# 12-Power-P3V3.net
KiCad netlist of a schematic drawn in Altium Designer
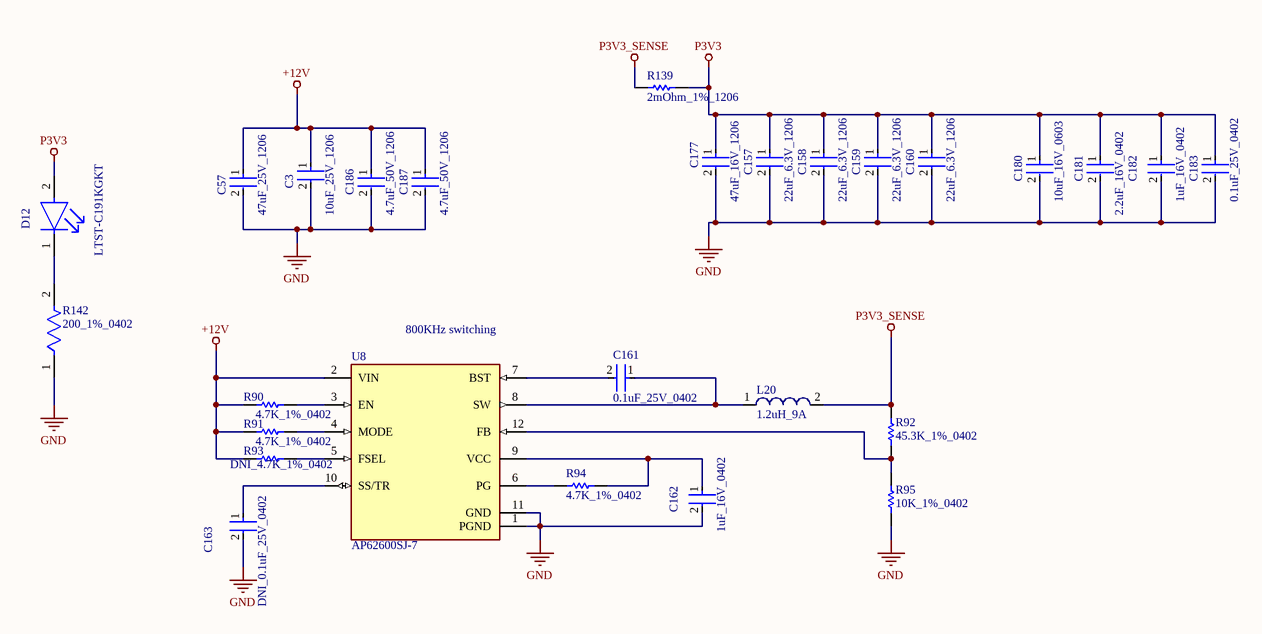
[diagram p0: 12-Power-P3V3.SchDoc]

(export (version "E")
  (design (tool "Eeschema 10.0.6"))
  (components
    (comp (ref "C3")
      (value "10uF_25V_1206")
      (footprint "FP-1206-L_3_2_0_2-W_1_6_0-IPC_A")
      (description "General Purpose Ceramic Capacitor, 1206, 10uF, 20%, X5R, 15%, 25V")
      (fields (field (name "TOLERANCE") "20%"))
      (libsource (lib "Altium Content Vault") (part "02cd4be3c70576c341d710602a673aa"))
    )
    (comp (ref "C57")
      (value "47uF_25V_1206")
      (footprint "FP-C3216-160-0_2-MFG")
      (description "Multilayer Ceramic Capacitors 47uF ±20% 25V X5R SMD 1206")
      (fields (field (name "VOLTAGE") "25V") (field (name "TOLERANCE") "20%"))
      (libsource (lib "Altium Content Vault") (part "11868f565c42a9108669ba33697ecf6"))
    )
    (comp (ref "C157")
      (value "22uF_6.3V_1206")
      (footprint "FP-1206-L_3_2_0_2-W_1_6_0-IPC_C")
      (description "General Purpose Ceramic Capacitor, 1206, 22uF, 20%, X5R, 15%, 6.3V")
      (fields (field (name "TOLERANCE") "20%") (field (name "VOLTAGE") "6.3V"))
      (libsource (lib "Altium Content Vault") (part "02cd4be3c70576c341d710602a673aa"))
    )
    (comp (ref "C158")
      (value "22uF_6.3V_1206")
      (footprint "FP-1206-L_3_2_0_2-W_1_6_0-IPC_C")
      (description "General Purpose Ceramic Capacitor, 1206, 22uF, 20%, X5R, 15%, 6.3V")
      (fields (field (name "TOLERANCE") "20%") (field (name "VOLTAGE") "6.3V"))
      (libsource (lib "Altium Content Vault") (part "02cd4be3c70576c341d710602a673aa"))
    )
    (comp (ref "C159")
      (value "22uF_6.3V_1206")
      (footprint "FP-1206-L_3_2_0_2-W_1_6_0-IPC_C")
      (description "General Purpose Ceramic Capacitor, 1206, 22uF, 20%, X5R, 15%, 6.3V")
      (fields (field (name "TOLERANCE") "20%") (field (name "VOLTAGE") "6.3V"))
      (libsource (lib "Altium Content Vault") (part "02cd4be3c70576c341d710602a673aa"))
    )
    (comp (ref "C160")
      (value "22uF_6.3V_1206")
      (footprint "FP-1206-L_3_2_0_2-W_1_6_0-IPC_C")
      (description "General Purpose Ceramic Capacitor, 1206, 22uF, 20%, X5R, 15%, 6.3V")
      (fields (field (name "TOLERANCE") "20%") (field (name "VOLTAGE") "6.3V"))
      (libsource (lib "Altium Content Vault") (part "02cd4be3c70576c341d710602a673aa"))
    )
    (comp (ref "C161")
      (value "0.1uF_25V_0402")
      (footprint "FP-0402-L_1_0_1-W_0_5_0_1-IPC_C")
      (description "General Purpose Ceramic Capacitor, 0402, 100nF, 10%, X7R, 15%, 25V")
      (fields (field (name "VOLTAGE") "25V") (field (name "TOLERANCE") "10%"))
      (libsource (lib "Altium Content Vault") (part "b4654b650e69147ec39a6b967a45e02"))
    )
    (comp (ref "C162")
      (value "1uF_16V_0402")
      (footprint "FP-0402-L_1_0_0_05-W_0_5-IPC_A")
      (description "None")
      (fields (field (name "TOLERANCE") "10%"))
      (libsource (lib "Altium Content Vault") (part "b4654b650e69147ec39a6b967a45e02"))
    )
    (comp (ref "C163")
      (value "DNI_0.1uF_25V_0402")
      (footprint "FP-0402-L_1_0_1-W_0_5_0_1-IPC_C")
      (description "General Purpose Ceramic Capacitor, 0402, 100nF, 10%, X7R, 15%, 25V")
      (fields (field (name "VOLTAGE") "25V") (field (name "TOLERANCE") "10%"))
      (libsource (lib "Altium Content Vault") (part "b4654b650e69147ec39a6b967a45e02"))
    )
    (comp (ref "C177")
      (value "47uF_16V_1206")
      (footprint "FP-C3216-160-0_2-MFG")
      (description "Multilayer Ceramic Capacitors 47uF ±20% 16V X5R SMD 1206")
      (fields (field (name "TOLERANCE") "20%"))
      (libsource (lib "Altium Content Vault") (part "11868f565c42a9108669ba33697ecf6"))
    )
    (comp (ref "C180")
      (value "10uF_16V_0603")
      (footprint "FP-0603-L_1_6_0_2-W_0_8_0-MFG")
      (description "Multilayer Ceramic Capacitor 10uF 16V X5R 20% SMD 0603 T/R")
      (fields (field (name "TOLERANCE") "20%"))
      (libsource (lib "Altium Content Vault") (part "b4654b650e69147ec39a6b967a45e02"))
    )
    (comp (ref "C181")
      (value "2.2uF_16V_0402")
      (footprint "FP-C1005-050-0_05-IPC_A")
      (description "Multilayer Ceramic Capacitors 2.2μF ±10% 16V X5R SMD 0402")
      (fields (field (name "TOLERANCE") "10%"))
      (libsource (lib "Altium Content Vault") (part "b4654b650e69147ec39a6b967a45e02"))
    )
    (comp (ref "C182")
      (value "1uF_16V_0402")
      (footprint "FP-0402-L_1_0_0_05-W_0_5-IPC_A")
      (description "None")
      (fields (field (name "TOLERANCE") "10%"))
      (libsource (lib "Altium Content Vault") (part "b4654b650e69147ec39a6b967a45e02"))
    )
    (comp (ref "C183")
      (value "0.1uF_25V_0402")
      (footprint "FP-0402-L_1_0_1-W_0_5_0_1-IPC_C")
      (description "General Purpose Ceramic Capacitor, 0402, 100nF, 10%, X7R, 15%, 25V")
      (fields (field (name "VOLTAGE") "25V") (field (name "TOLERANCE") "10%"))
      (libsource (lib "Altium Content Vault") (part "b4654b650e69147ec39a6b967a45e02"))
    )
    (comp (ref "C186")
      (value "4.7uF_50V_1206")
      (footprint "FP-GRM31C-0_2-e0_3_0_8-IPC_C")
      (description "Chip Multilayer Ceramic Capacitors for General Purpose, 1206, 4.7uF, X7R, 15%, 10%, 50V")
      (fields (field (name "VOLTAGE") "50V") (field (name "TOLERANCE") "10%"))
      (libsource (lib "Altium Content Vault") (part "02cd4be3c70576c341d710602a673aa"))
    )
    (comp (ref "C187")
      (value "4.7uF_50V_1206")
      (footprint "FP-GRM31C-0_2-e0_3_0_8-IPC_C")
      (description "Chip Multilayer Ceramic Capacitors for General Purpose, 1206, 4.7uF, X7R, 15%, 10%, 50V")
      (fields (field (name "VOLTAGE") "50V") (field (name "TOLERANCE") "10%"))
      (libsource (lib "Altium Content Vault") (part "02cd4be3c70576c341d710602a673aa"))
    )
    (comp (ref "D12")
      (value "LTST-C191KGKT")
      (footprint "FP-LTST-C191KGKT-MFG")
      (description "LED GREEN CLEAR SMD")
      (libsource (lib "Altium Content Vault") (part "8706943c75ba83719d021d2fdc84c58"))
    )
    (comp (ref "L20")
      (value "1.2uH_9A")
      (footprint "WE-LHMI 7050")
      (description "SMD Power Inductor WE-LHMI, L=1.2 µH")
      (fields (field (name "MANUFACTURER") "Wuerth Elektronik") (field (name "PARTNUMBER") "74437349012"))
      (libsource (lib "Altium Content Vault") (part "WE-IND-INDUCTOR-2"))
    )
    (comp (ref "R90")
      (value "4.7K_1%_0402")
      (footprint "RESC1005X40X25NL10T10")
      (fields (field (name "MANUFACTURER") "Bourns") (field (name "PART NUMBER") "CR0402-FX-4701GLF"))
      (libsource (lib "Altium Content Vault") (part "RES"))
    )
    (comp (ref "R91")
      (value "4.7K_1%_0402")
      (footprint "RESC1005X40X25NL10T10")
      (fields (field (name "MANUFACTURER") "Bourns") (field (name "PART NUMBER") "CR0402-FX-4701GLF"))
      (libsource (lib "Altium Content Vault") (part "RES"))
    )
    (comp (ref "R92")
      (value "45.3K_1%_0402")
      (footprint "RESC1005X40X25ML05T10")
      (fields (field (name "PART NUMBER") "RC0402FR-0745K3L") (field (name "MANUFACTURER") "Yageo / Phycomp"))
      (libsource (lib "Altium Content Vault") (part "RES"))
    )
    (comp (ref "R93")
      (value "DNI_4.7K_1%_0402")
      (footprint "RESC1005X40X25NL10T10")
      (fields (field (name "MANUFACTURER") "Bourns") (field (name "PART NUMBER") "CR0402-FX-4701GLF"))
      (libsource (lib "Altium Content Vault") (part "RES"))
    )
    (comp (ref "R94")
      (value "4.7K_1%_0402")
      (footprint "RESC1005X40X25NL10T10")
      (fields (field (name "MANUFACTURER") "Bourns") (field (name "PART NUMBER") "CR0402-FX-4701GLF"))
      (libsource (lib "Altium Content Vault") (part "RES"))
    )
    (comp (ref "R95")
      (value "10K_1%_0402")
      (footprint "RESC1005X40X25NL10T10")
      (fields (field (name "MANUFACTURER") "Bourns") (field (name "PART NUMBER") "CR0402-FX-1002GLF"))
      (libsource (lib "Altium Content Vault") (part "RES"))
    )
    (comp (ref "R139")
      (value "2mOhm_1%_1206")
      (footprint "RESC3216X89X64NL25T25")
      (fields (field (name "MANUFACTURER") "Vishay Dale") (field (name "PART NUMBER") "WSL12062L000FEA18"))
      (libsource (lib "Altium Content Vault") (part "RES"))
    )
    (comp (ref "R142")
      (value "200_1%_0402")
      (footprint "FP-ERJ2RK-IPC_A")
      (description "RES SMD 200 OHM 1% 1/10W 0402")
      (fields (field (name "TOLERANCE") "1%"))
      (libsource (lib "Altium Content Vault") (part "1029c3af85768c4190bb7ad29bc67b5"))
    )
    (comp (ref "U8")
      (value "AP62600SJ-7")
      (footprint "FP-V-QFN2030-12_Type_A-MFG")
      (description "DCDC CONV HV BUCK,V-QFN2030-12")
      (libsource (lib "Altium Content Vault") (part "03c86ce2703f4b33b3045e94f7be521"))
    )
  )
  (nets
    (net (code "1") (name "+12V") (class "Default")
      (node (ref "C186") (pin "1") (pinfunction "1_1") (pintype "passive"))
      (node (ref "C187") (pin "1") (pinfunction "1_1") (pintype "passive"))
      (node (ref "C3") (pin "1") (pinfunction "1_1") (pintype "passive"))
      (node (ref "C57") (pin "1") (pinfunction "1_1") (pintype "passive"))
      (node (ref "R90") (pin "1") (pinfunction "1_1") (pintype "passive"))
      (node (ref "R91") (pin "1") (pinfunction "1_1") (pintype "passive"))
      (node (ref "R93") (pin "1") (pinfunction "1_1") (pintype "passive"))
      (node (ref "U8") (pin "2") (pinfunction "VIN_2") (pintype "power_in"))
    )
    (net (code "2") (name "GND") (class "Default")
      (node (ref "C157") (pin "2") (pinfunction "2_2") (pintype "passive"))
      (node (ref "C158") (pin "2") (pinfunction "2_2") (pintype "passive"))
      (node (ref "C159") (pin "2") (pinfunction "2_2") (pintype "passive"))
      (node (ref "C160") (pin "2") (pinfunction "2_2") (pintype "passive"))
      (node (ref "C162") (pin "2") (pinfunction "2_2") (pintype "passive"))
      (node (ref "C163") (pin "2") (pinfunction "2_2") (pintype "passive"))
      (node (ref "C177") (pin "2") (pinfunction "2_2") (pintype "passive"))
      (node (ref "C180") (pin "2") (pinfunction "2_2") (pintype "passive"))
      (node (ref "C181") (pin "2") (pinfunction "2_2") (pintype "passive"))
      (node (ref "C182") (pin "2") (pinfunction "2_2") (pintype "passive"))
      (node (ref "C183") (pin "2") (pinfunction "2_2") (pintype "passive"))
      (node (ref "C186") (pin "2") (pinfunction "2_2") (pintype "passive"))
      (node (ref "C187") (pin "2") (pinfunction "2_2") (pintype "passive"))
      (node (ref "C3") (pin "2") (pinfunction "2_2") (pintype "passive"))
      (node (ref "C57") (pin "2") (pinfunction "2_2") (pintype "passive"))
      (node (ref "R142") (pin "1") (pinfunction "1_1") (pintype "passive"))
      (node (ref "R95") (pin "1") (pinfunction "1_1") (pintype "passive"))
      (node (ref "U8") (pin "1") (pinfunction "PGND_1") (pintype "power_in"))
      (node (ref "U8") (pin "11") (pinfunction "GND_11") (pintype "power_in"))
    )
    (net (code "3") (name "Net-(D12-C)") (class "Default")
      (node (ref "D12") (pin "1") (pinfunction "C_1") (pintype "passive"))
      (node (ref "R142") (pin "2") (pinfunction "2_2") (pintype "passive"))
    )
    (net (code "4") (name "Net-(U8-BST)") (class "Default")
      (node (ref "C161") (pin "2") (pinfunction "2_2") (pintype "passive"))
      (node (ref "U8") (pin "7") (pinfunction "BST_7") (pintype "input"))
    )
    (net (code "5") (name "Net-(U8-EN)") (class "Default")
      (node (ref "R90") (pin "2") (pinfunction "2_2") (pintype "passive"))
      (node (ref "U8") (pin "3") (pinfunction "EN_3") (pintype "input"))
    )
    (net (code "6") (name "Net-(U8-FB)") (class "Default")
      (node (ref "R92") (pin "1") (pinfunction "1_1") (pintype "passive"))
      (node (ref "R95") (pin "2") (pinfunction "2_2") (pintype "passive"))
      (node (ref "U8") (pin "12") (pinfunction "FB_12") (pintype "input"))
    )
    (net (code "7") (name "Net-(U8-FSEL)") (class "Default")
      (node (ref "R93") (pin "2") (pinfunction "2_2") (pintype "passive"))
      (node (ref "U8") (pin "5") (pinfunction "FSEL_5") (pintype "input"))
    )
    (net (code "8") (name "Net-(U8-MODE)") (class "Default")
      (node (ref "R91") (pin "2") (pinfunction "2_2") (pintype "passive"))
      (node (ref "U8") (pin "4") (pinfunction "MODE_4") (pintype "input"))
    )
    (net (code "9") (name "Net-(U8-PG)") (class "Default")
      (node (ref "R94") (pin "2") (pinfunction "2_2") (pintype "passive"))
      (node (ref "U8") (pin "6") (pinfunction "PG_6") (pintype "open_collector"))
    )
    (net (code "10") (name "Net-(U8-SS{slash}TR)") (class "Default")
      (node (ref "C163") (pin "1") (pinfunction "1_1") (pintype "passive"))
      (node (ref "U8") (pin "10") (pinfunction "SS/TR_10") (pintype "bidirectional"))
    )
    (net (code "11") (name "Net-(U8-SW)") (class "Default")
      (node (ref "C161") (pin "1") (pinfunction "1_1") (pintype "passive"))
      (node (ref "L20") (pin "1") (pinfunction "1_1") (pintype "passive"))
      (node (ref "U8") (pin "8") (pinfunction "SW_8") (pintype "output"))
    )
    (net (code "12") (name "Net-(U8-VCC)") (class "Default")
      (node (ref "C162") (pin "1") (pinfunction "1_1") (pintype "passive"))
      (node (ref "R94") (pin "1") (pinfunction "1_1") (pintype "passive"))
      (node (ref "U8") (pin "9") (pinfunction "VCC_9") (pintype "power_in"))
    )
    (net (code "13") (name "P3V3") (class "Default")
      (node (ref "C157") (pin "1") (pinfunction "1_1") (pintype "passive"))
      (node (ref "C158") (pin "1") (pinfunction "1_1") (pintype "passive"))
      (node (ref "C159") (pin "1") (pinfunction "1_1") (pintype "passive"))
      (node (ref "C160") (pin "1") (pinfunction "1_1") (pintype "passive"))
      (node (ref "C177") (pin "1") (pinfunction "1_1") (pintype "passive"))
      (node (ref "C180") (pin "1") (pinfunction "1_1") (pintype "passive"))
      (node (ref "C181") (pin "1") (pinfunction "1_1") (pintype "passive"))
      (node (ref "C182") (pin "1") (pinfunction "1_1") (pintype "passive"))
      (node (ref "C183") (pin "1") (pinfunction "1_1") (pintype "passive"))
      (node (ref "D12") (pin "2") (pinfunction "A_2") (pintype "passive"))
      (node (ref "R139") (pin "2") (pinfunction "2_2") (pintype "passive"))
    )
    (net (code "14") (name "P3V3_SENSE") (class "Default")
      (node (ref "L20") (pin "2") (pinfunction "2_2") (pintype "passive"))
      (node (ref "R139") (pin "1") (pinfunction "1_1") (pintype "passive"))
      (node (ref "R92") (pin "2") (pinfunction "2_2") (pintype "passive"))
    )
  )
)
